# powergig.net
KiCad netlist of a schematic drawn in EAGLE
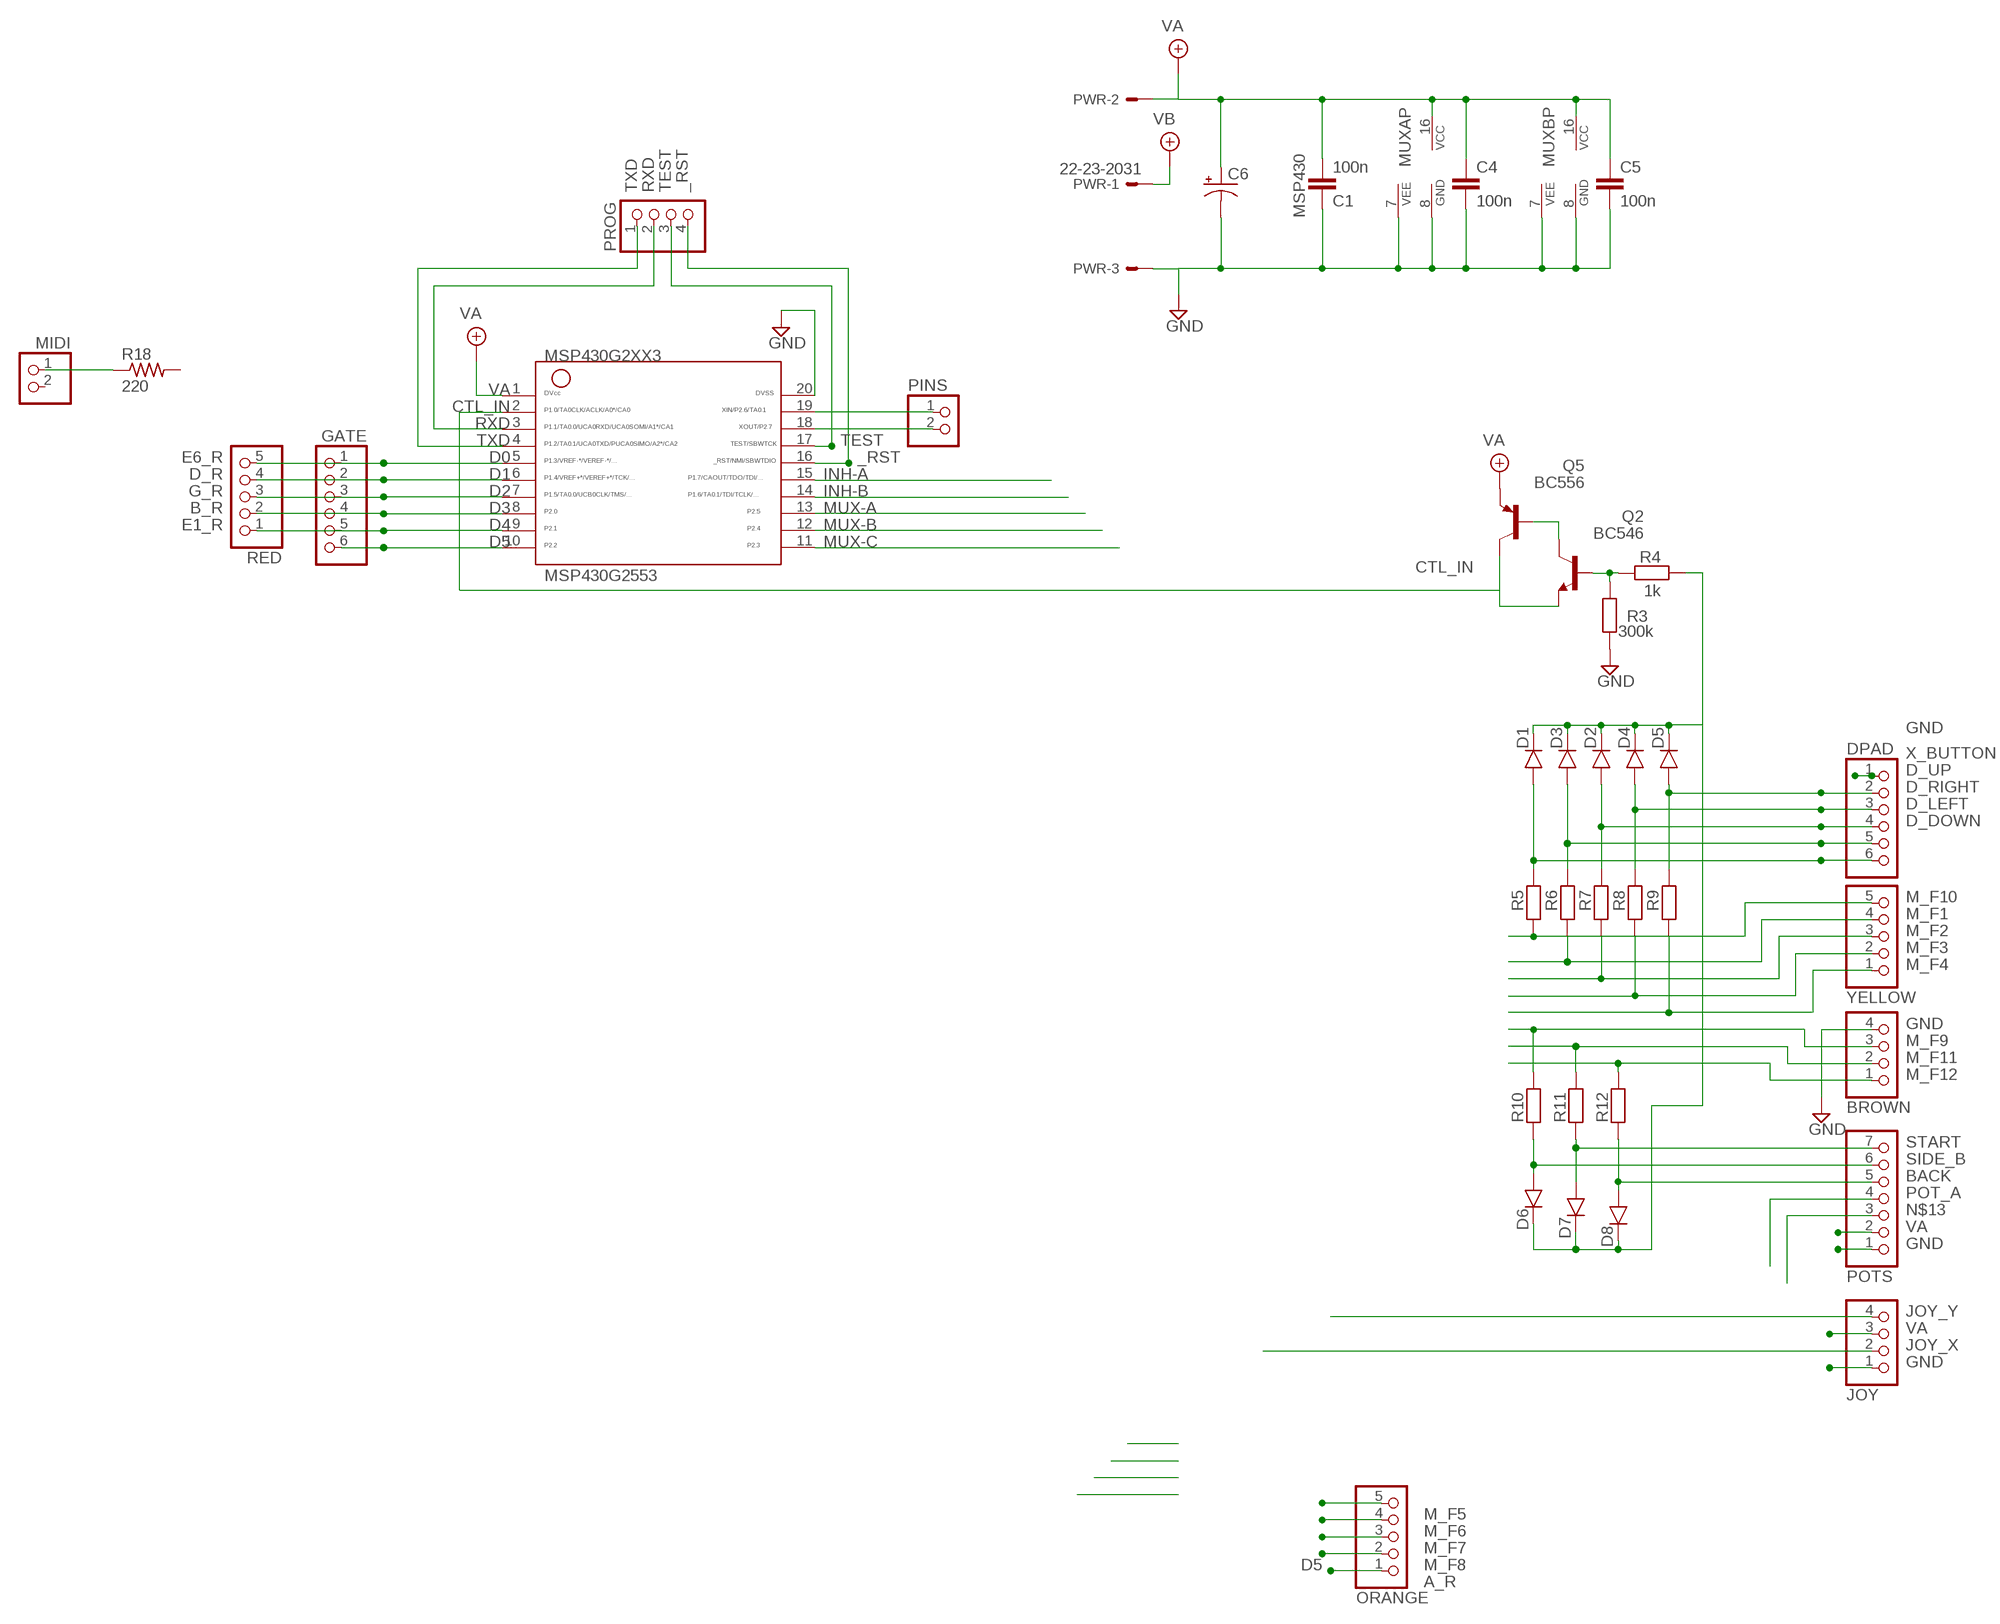
[diagram p0: schematic, sheet 1]

(export (version "E")
  (design (tool "Eeschema 10.0.6"))
  (components
    (comp (ref "BROWN")
      (value "PINHD-1X4")
      (footprint "eagle-import:1X04")
      (libsource (lib "eagle-import") (part "PINHD-1X4"))
    )
    (comp (ref "C1")
      (value "100n")
      (footprint "eagle-import:050X030_050_3")
      (libsource (lib "eagle-import") (part "050X030_050"))
    )
    (comp (ref "C4")
      (value "100n")
      (footprint "eagle-import:050X030_050_1")
      (libsource (lib "eagle-import") (part "050X030_0501"))
    )
    (comp (ref "C5")
      (value "100n")
      (footprint "eagle-import:050X030_050_3")
      (libsource (lib "eagle-import") (part "050X030_050"))
    )
    (comp (ref "C6")
      (value "0501")
      (footprint "eagle-import:050_020_1")
      (libsource (lib "eagle-import") (part "0501"))
    )
    (comp (ref "D1")
      (value "1N4148-2")
      (footprint "eagle-import:DO35-2")
      (libsource (lib "eagle-import") (part "1N4148-2"))
    )
    (comp (ref "D2")
      (value "1N4148-2")
      (footprint "eagle-import:DO35-2")
      (libsource (lib "eagle-import") (part "1N4148-2"))
    )
    (comp (ref "D3")
      (value "1N4148-2")
      (footprint "eagle-import:DO35-2")
      (libsource (lib "eagle-import") (part "1N4148-2"))
    )
    (comp (ref "D4")
      (value "1N4148-2")
      (footprint "eagle-import:DO35-2")
      (libsource (lib "eagle-import") (part "1N4148-2"))
    )
    (comp (ref "D5")
      (value "1N4148-2")
      (footprint "eagle-import:DO35-2")
      (libsource (lib "eagle-import") (part "1N4148-2"))
    )
    (comp (ref "D6")
      (value "1N4148-2")
      (footprint "eagle-import:DO35-2")
      (libsource (lib "eagle-import") (part "1N4148-2"))
    )
    (comp (ref "D7")
      (value "1N4148-2")
      (footprint "eagle-import:DO35-2")
      (libsource (lib "eagle-import") (part "1N4148-2"))
    )
    (comp (ref "D8")
      (value "1N4148-2")
      (footprint "eagle-import:DO35-2")
      (libsource (lib "eagle-import") (part "1N4148-2"))
    )
    (comp (ref "DPAD")
      (value "PINHD-1X6")
      (footprint "eagle-import:1X06")
      (libsource (lib "eagle-import") (part "PINHD-1X6"))
    )
    (comp (ref "GATE")
      (value "PINHD-1X6")
      (footprint "eagle-import:1X06")
      (libsource (lib "eagle-import") (part "PINHD-1X6"))
    )
    (comp (ref "JOY")
      (value "PINHD-1X4")
      (footprint "eagle-import:1X04")
      (libsource (lib "eagle-import") (part "PINHD-1X4"))
    )
    (comp (ref "MIDI")
      (value "PINHD-1X2")
      (footprint "eagle-import:1X02")
      (libsource (lib "eagle-import") (part "PINHD-1X2"))
    )
    (comp (ref "MSP430G2553")
      (value "G2XX3---N20")
      (footprint "eagle-import:N20")
      (libsource (lib "eagle-import") (part "G2XX3---N20"))
    )
    (comp (ref "MUXA")
      (value "4051N")
      (footprint "eagle-import:DIL16")
      (libsource (lib "eagle-import") (part "4051N"))
    )
    (comp (ref "MUXB")
      (value "4052N")
      (footprint "eagle-import:DIL16")
      (libsource (lib "eagle-import") (part "4052N"))
    )
    (comp (ref "ORANGE")
      (value "PINHD-1X5")
      (footprint "eagle-import:1X05")
      (libsource (lib "eagle-import") (part "PINHD-1X5"))
    )
    (comp (ref "PINS")
      (value "PINHD-1X2")
      (footprint "eagle-import:1X02")
      (libsource (lib "eagle-import") (part "PINHD-1X2"))
    )
    (comp (ref "POTS")
      (value "PINHD-1X7")
      (footprint "eagle-import:1X07")
      (libsource (lib "eagle-import") (part "PINHD-1X7"))
    )
    (comp (ref "PROG")
      (value "PINHD-1X4")
      (footprint "eagle-import:1X04")
      (libsource (lib "eagle-import") (part "PINHD-1X4"))
    )
    (comp (ref "PWR")
      (value "22-23-2031")
      (footprint "eagle-import:22-23-2031")
      (fields (field (name "MF") "MOLEX"))
      (libsource (lib "eagle-import") (part "22-23-2031"))
    )
    (comp (ref "Q2")
      (value "BC546")
      (footprint "eagle-import:TO92-EBC")
      (libsource (lib "eagle-import") (part "BC546B"))
    )
    (comp (ref "Q5")
      (value "BC556")
      (footprint "eagle-import:TO92-EBC")
      (libsource (lib "eagle-import") (part "BC556"))
    )
    (comp (ref "R3")
      (value "300k")
      (footprint "eagle-import:R0207_1V")
      (libsource (lib "eagle-import") (part "6MM-EU1"))
    )
    (comp (ref "R4")
      (value "1k")
      (footprint "eagle-import:R0207_3")
      (libsource (lib "eagle-import") (part "6MM-EU"))
    )
    (comp (ref "R5")
      (value "30k")
      (footprint "eagle-import:R0207_1V")
      (libsource (lib "eagle-import") (part "6MM-EU1"))
    )
    (comp (ref "R6")
      (value "30k")
      (footprint "eagle-import:R0207_1V")
      (libsource (lib "eagle-import") (part "6MM-EU1"))
    )
    (comp (ref "R7")
      (value "30k")
      (footprint "eagle-import:R0207_1V")
      (libsource (lib "eagle-import") (part "6MM-EU1"))
    )
    (comp (ref "R8")
      (value "30k")
      (footprint "eagle-import:R0207_1V")
      (libsource (lib "eagle-import") (part "6MM-EU1"))
    )
    (comp (ref "R9")
      (value "30k")
      (footprint "eagle-import:R0207_1V")
      (libsource (lib "eagle-import") (part "6MM-EU1"))
    )
    (comp (ref "R10")
      (value "30k")
      (footprint "eagle-import:R0207_2V")
      (libsource (lib "eagle-import") (part "6MM-EU2"))
    )
    (comp (ref "R11")
      (value "30k")
      (footprint "eagle-import:R0207_2V")
      (libsource (lib "eagle-import") (part "6MM-EU2"))
    )
    (comp (ref "R12")
      (value "30k")
      (footprint "eagle-import:R0207_2V")
      (libsource (lib "eagle-import") (part "6MM-EU2"))
    )
    (comp (ref "R18")
      (value "220")
      (footprint "eagle-import:R0207_3")
      (libsource (lib "eagle-import") (part "6MM.3"))
    )
    (comp (ref "RED")
      (value "PINHD-1X5")
      (footprint "eagle-import:1X05")
      (libsource (lib "eagle-import") (part "PINHD-1X5"))
    )
    (comp (ref "YELLOW")
      (value "PINHD-1X5")
      (footprint "eagle-import:1X05")
      (libsource (lib "eagle-import") (part "PINHD-1X5"))
    )
  )
  (nets
    (net (code "1") (name "/BACK") (class "Default")
      (node (ref "D7") (pin "A") (pinfunction "A_A") (pintype "passive"))
      (node (ref "POTS") (pin "7") (pinfunction "7_7") (pintype "passive"))
      (node (ref "R11") (pin "2") (pinfunction "2_2") (pintype "passive"))
    )
    (net (code "2") (name "/CTL_IN") (class "Default")
      (node (ref "MSP430G2553") (pin "2") (pinfunction "2_2") (pintype "bidirectional"))
      (node (ref "Q2") (pin "E") (pinfunction "E_E") (pintype "passive"))
      (node (ref "Q5") (pin "C") (pinfunction "C_C") (pintype "passive"))
    )
    (net (code "3") (name "/D0") (class "Default")
      (node (ref "GATE") (pin "1") (pinfunction "1_1") (pintype "passive"))
      (node (ref "MSP430G2553") (pin "5") (pinfunction "5_5") (pintype "bidirectional"))
      (node (ref "RED") (pin "5") (pinfunction "5_5") (pintype "passive"))
    )
    (net (code "4") (name "/D1") (class "Default")
      (node (ref "GATE") (pin "2") (pinfunction "2_2") (pintype "passive"))
      (node (ref "MSP430G2553") (pin "6") (pinfunction "6_6") (pintype "bidirectional"))
      (node (ref "RED") (pin "4") (pinfunction "4_4") (pintype "passive"))
    )
    (net (code "5") (name "/D2") (class "Default")
      (node (ref "GATE") (pin "3") (pinfunction "3_3") (pintype "passive"))
      (node (ref "MSP430G2553") (pin "7") (pinfunction "7_7") (pintype "bidirectional"))
      (node (ref "RED") (pin "3") (pinfunction "3_3") (pintype "passive"))
    )
    (net (code "6") (name "/D3") (class "Default")
      (node (ref "GATE") (pin "4") (pinfunction "4_4") (pintype "passive"))
      (node (ref "MSP430G2553") (pin "8") (pinfunction "8_8") (pintype "bidirectional"))
      (node (ref "RED") (pin "2") (pinfunction "2_2") (pintype "passive"))
    )
    (net (code "7") (name "/D4") (class "Default")
      (node (ref "GATE") (pin "5") (pinfunction "5_5") (pintype "passive"))
      (node (ref "MSP430G2553") (pin "9") (pinfunction "9_9") (pintype "bidirectional"))
      (node (ref "RED") (pin "1") (pinfunction "1_1") (pintype "passive"))
    )
    (net (code "8") (name "/D5") (class "Default")
      (node (ref "GATE") (pin "6") (pinfunction "6_6") (pintype "passive"))
      (node (ref "MSP430G2553") (pin "10") (pinfunction "10_10") (pintype "bidirectional"))
      (node (ref "ORANGE") (pin "1") (pinfunction "1_1") (pintype "passive"))
    )
    (net (code "9") (name "/D_DOWN") (class "Default")
      (node (ref "D1") (pin "A") (pinfunction "A_A") (pintype "passive"))
      (node (ref "DPAD") (pin "6") (pinfunction "6_6") (pintype "passive"))
      (node (ref "R5") (pin "2") (pinfunction "2_2") (pintype "passive"))
    )
    (net (code "10") (name "/D_LEFT") (class "Default")
      (node (ref "D3") (pin "A") (pinfunction "A_A") (pintype "passive"))
      (node (ref "DPAD") (pin "5") (pinfunction "5_5") (pintype "passive"))
      (node (ref "R6") (pin "2") (pinfunction "2_2") (pintype "passive"))
    )
    (net (code "11") (name "/D_RIGHT") (class "Default")
      (node (ref "D2") (pin "A") (pinfunction "A_A") (pintype "passive"))
      (node (ref "DPAD") (pin "4") (pinfunction "4_4") (pintype "passive"))
      (node (ref "R7") (pin "2") (pinfunction "2_2") (pintype "passive"))
    )
    (net (code "12") (name "/D_UP") (class "Default")
      (node (ref "D4") (pin "A") (pinfunction "A_A") (pintype "passive"))
      (node (ref "DPAD") (pin "3") (pinfunction "3_3") (pintype "passive"))
      (node (ref "R8") (pin "2") (pinfunction "2_2") (pintype "passive"))
    )
    (net (code "13") (name "/INH-A") (class "Default")
      (node (ref "MSP430G2553") (pin "15") (pinfunction "15_15") (pintype "bidirectional"))
    )
    (net (code "14") (name "/INH-B") (class "Default")
      (node (ref "MSP430G2553") (pin "14") (pinfunction "14_14") (pintype "bidirectional"))
    )
    (net (code "15") (name "/JOY_X") (class "Default")
      (node (ref "JOY") (pin "2") (pinfunction "2_2") (pintype "passive"))
    )
    (net (code "16") (name "/JOY_Y") (class "Default")
      (node (ref "JOY") (pin "4") (pinfunction "4_4") (pintype "passive"))
    )
    (net (code "17") (name "/MUX-A") (class "Default")
      (node (ref "MSP430G2553") (pin "13") (pinfunction "13_13") (pintype "bidirectional"))
    )
    (net (code "18") (name "/MUX-B") (class "Default")
      (node (ref "MSP430G2553") (pin "12") (pinfunction "12_12") (pintype "bidirectional"))
    )
    (net (code "19") (name "/MUX-C") (class "Default")
      (node (ref "MSP430G2553") (pin "11") (pinfunction "11_11") (pintype "bidirectional"))
    )
    (net (code "20") (name "/M_F1") (class "Default")
      (node (ref "R6") (pin "1") (pinfunction "1_1") (pintype "passive"))
      (node (ref "YELLOW") (pin "4") (pinfunction "4_4") (pintype "passive"))
    )
    (net (code "21") (name "/M_F2") (class "Default")
      (node (ref "R7") (pin "1") (pinfunction "1_1") (pintype "passive"))
      (node (ref "YELLOW") (pin "3") (pinfunction "3_3") (pintype "passive"))
    )
    (net (code "22") (name "/M_F3") (class "Default")
      (node (ref "R8") (pin "1") (pinfunction "1_1") (pintype "passive"))
      (node (ref "YELLOW") (pin "2") (pinfunction "2_2") (pintype "passive"))
    )
    (net (code "23") (name "/M_F4") (class "Default")
      (node (ref "R9") (pin "1") (pinfunction "1_1") (pintype "passive"))
      (node (ref "YELLOW") (pin "1") (pinfunction "1_1") (pintype "passive"))
    )
    (net (code "24") (name "/M_F5") (class "Default")
      (node (ref "ORANGE") (pin "5") (pinfunction "5_5") (pintype "passive"))
    )
    (net (code "25") (name "/M_F6") (class "Default")
      (node (ref "ORANGE") (pin "4") (pinfunction "4_4") (pintype "passive"))
    )
    (net (code "26") (name "/M_F7") (class "Default")
      (node (ref "ORANGE") (pin "3") (pinfunction "3_3") (pintype "passive"))
    )
    (net (code "27") (name "/M_F8") (class "Default")
      (node (ref "ORANGE") (pin "2") (pinfunction "2_2") (pintype "passive"))
    )
    (net (code "28") (name "/M_F9") (class "Default")
      (node (ref "BROWN") (pin "3") (pinfunction "3_3") (pintype "passive"))
      (node (ref "R10") (pin "1") (pinfunction "1_1") (pintype "passive"))
    )
    (net (code "29") (name "/M_F10") (class "Default")
      (node (ref "R5") (pin "1") (pinfunction "1_1") (pintype "passive"))
      (node (ref "YELLOW") (pin "5") (pinfunction "5_5") (pintype "passive"))
    )
    (net (code "30") (name "/M_F11") (class "Default")
      (node (ref "BROWN") (pin "2") (pinfunction "2_2") (pintype "passive"))
      (node (ref "R11") (pin "1") (pinfunction "1_1") (pintype "passive"))
    )
    (net (code "31") (name "/M_F12") (class "Default")
      (node (ref "BROWN") (pin "1") (pinfunction "1_1") (pintype "passive"))
      (node (ref "R12") (pin "1") (pinfunction "1_1") (pintype "passive"))
    )
    (net (code "32") (name "/N$13") (class "Default")
      (node (ref "POTS") (pin "3") (pinfunction "3_3") (pintype "passive"))
    )
    (net (code "33") (name "/POT_A") (class "Default")
      (node (ref "POTS") (pin "4") (pinfunction "4_4") (pintype "passive"))
    )
    (net (code "34") (name "/RXD") (class "Default")
      (node (ref "MSP430G2553") (pin "3") (pinfunction "3_3") (pintype "bidirectional"))
      (node (ref "PROG") (pin "2") (pinfunction "2_2") (pintype "passive"))
    )
    (net (code "35") (name "/SIDE_B") (class "Default")
      (node (ref "D6") (pin "A") (pinfunction "A_A") (pintype "passive"))
      (node (ref "POTS") (pin "6") (pinfunction "6_6") (pintype "passive"))
      (node (ref "R10") (pin "2") (pinfunction "2_2") (pintype "passive"))
    )
    (net (code "36") (name "/START") (class "Default")
      (node (ref "D8") (pin "A") (pinfunction "A_A") (pintype "passive"))
      (node (ref "POTS") (pin "5") (pinfunction "5_5") (pintype "passive"))
      (node (ref "R12") (pin "2") (pinfunction "2_2") (pintype "passive"))
    )
    (net (code "37") (name "/TEST") (class "Default")
      (node (ref "MSP430G2553") (pin "17") (pinfunction "17_17") (pintype "bidirectional"))
      (node (ref "PROG") (pin "3") (pinfunction "3_3") (pintype "passive"))
    )
    (net (code "38") (name "/TXD") (class "Default")
      (node (ref "MSP430G2553") (pin "4") (pinfunction "4_4") (pintype "bidirectional"))
      (node (ref "PROG") (pin "1") (pinfunction "1_1") (pintype "passive"))
    )
    (net (code "39") (name "/X_BUTTON") (class "Default")
      (node (ref "D5") (pin "A") (pinfunction "A_A") (pintype "passive"))
      (node (ref "DPAD") (pin "2") (pinfunction "2_2") (pintype "passive"))
      (node (ref "R9") (pin "2") (pinfunction "2_2") (pintype "passive"))
    )
    (net (code "40") (name "/_RST") (class "Default")
      (node (ref "MSP430G2553") (pin "16") (pinfunction "16_16") (pintype "bidirectional"))
      (node (ref "PROG") (pin "4") (pinfunction "4_4") (pintype "passive"))
    )
    (net (code "41") (name "GND") (class "Default")
      (node (ref "BROWN") (pin "4") (pinfunction "4_4") (pintype "passive"))
      (node (ref "C1") (pin "1") (pinfunction "1_1") (pintype "passive"))
      (node (ref "C4") (pin "2") (pinfunction "2_2") (pintype "passive"))
      (node (ref "C5") (pin "2") (pinfunction "2_2") (pintype "passive"))
      (node (ref "C6") (pin "-") (pinfunction "-_-") (pintype "passive"))
      (node (ref "DPAD") (pin "1") (pinfunction "1_1") (pintype "passive"))
      (node (ref "JOY") (pin "1") (pinfunction "1_1") (pintype "passive"))
      (node (ref "MSP430G2553") (pin "20") (pinfunction "20_20") (pintype "bidirectional"))
      (node (ref "MUXA") (pin "7") (pinfunction "VEE_7") (pintype "power_in"))
      (node (ref "MUXA") (pin "8") (pinfunction "GND_8") (pintype "power_in"))
      (node (ref "MUXB") (pin "7") (pinfunction "VEE_7") (pintype "power_in"))
      (node (ref "MUXB") (pin "8") (pinfunction "GND_8") (pintype "power_in"))
      (node (ref "POTS") (pin "1") (pinfunction "1_1") (pintype "passive"))
      (node (ref "PWR") (pin "3") (pinfunction "S_3") (pintype "passive"))
      (node (ref "R3") (pin "2") (pinfunction "2_2") (pintype "passive"))
    )
    (net (code "42") (name "Net-(D1-PadC)") (class "Default")
      (node (ref "D1") (pin "C") (pinfunction "C_C") (pintype "passive"))
      (node (ref "D2") (pin "C") (pinfunction "C_C") (pintype "passive"))
      (node (ref "D3") (pin "C") (pinfunction "C_C") (pintype "passive"))
      (node (ref "D4") (pin "C") (pinfunction "C_C") (pintype "passive"))
      (node (ref "D5") (pin "C") (pinfunction "C_C") (pintype "passive"))
      (node (ref "D6") (pin "C") (pinfunction "C_C") (pintype "passive"))
      (node (ref "D7") (pin "C") (pinfunction "C_C") (pintype "passive"))
      (node (ref "D8") (pin "C") (pinfunction "C_C") (pintype "passive"))
      (node (ref "R4") (pin "1") (pinfunction "1_1") (pintype "passive"))
    )
    (net (code "43") (name "Net-(MIDI-Pad1)") (class "Default")
      (node (ref "MIDI") (pin "1") (pinfunction "1_1") (pintype "passive"))
      (node (ref "R18") (pin "1") (pinfunction "1_1") (pintype "passive"))
    )
    (net (code "44") (name "Net-(MSP430G2553-Pad18)") (class "Default")
      (node (ref "MSP430G2553") (pin "18") (pinfunction "18_18") (pintype "bidirectional"))
      (node (ref "PINS") (pin "2") (pinfunction "2_2") (pintype "passive"))
    )
    (net (code "45") (name "Net-(MSP430G2553-Pad19)") (class "Default")
      (node (ref "MSP430G2553") (pin "19") (pinfunction "19_19") (pintype "bidirectional"))
      (node (ref "PINS") (pin "1") (pinfunction "1_1") (pintype "passive"))
    )
    (net (code "46") (name "Net-(Q2-PadB)") (class "Default")
      (node (ref "Q2") (pin "B") (pinfunction "B_B") (pintype "passive"))
      (node (ref "R3") (pin "1") (pinfunction "1_1") (pintype "passive"))
      (node (ref "R4") (pin "2") (pinfunction "2_2") (pintype "passive"))
    )
    (net (code "47") (name "Net-(Q2-PadC)") (class "Default")
      (node (ref "Q2") (pin "C") (pinfunction "C_C") (pintype "passive"))
      (node (ref "Q5") (pin "B") (pinfunction "B_B") (pintype "passive"))
    )
    (net (code "48") (name "VA") (class "Default")
      (node (ref "C1") (pin "2") (pinfunction "2_2") (pintype "passive"))
      (node (ref "C4") (pin "1") (pinfunction "1_1") (pintype "passive"))
      (node (ref "C5") (pin "1") (pinfunction "1_1") (pintype "passive"))
      (node (ref "C6") (pin "+") (pinfunction "+_+") (pintype "passive"))
      (node (ref "JOY") (pin "3") (pinfunction "3_3") (pintype "passive"))
      (node (ref "MSP430G2553") (pin "1") (pinfunction "1_1") (pintype "bidirectional"))
      (node (ref "MUXA") (pin "16") (pinfunction "VCC_16") (pintype "power_in"))
      (node (ref "MUXB") (pin "16") (pinfunction "VCC_16") (pintype "power_in"))
      (node (ref "POTS") (pin "2") (pinfunction "2_2") (pintype "passive"))
      (node (ref "PWR") (pin "2") (pinfunction "S_2") (pintype "passive"))
      (node (ref "Q5") (pin "E") (pinfunction "E_E") (pintype "passive"))
    )
    (net (code "49") (name "VB") (class "Default")
      (node (ref "PWR") (pin "1") (pinfunction "S_1") (pintype "passive"))
    )
    (net (code "50") (name "unconnected-(MIDI-Pad2)") (class "Default")
      (node (ref "MIDI") (pin "2") (pinfunction "2_2") (pintype "passive"))
    )
    (net (code "51") (name "unconnected-(R18-Pad2)") (class "Default")
      (node (ref "R18") (pin "2") (pinfunction "2_2") (pintype "passive"))
    )
  )
)
